# Mother_Board_ver2_0_0_under.net
KiCad netlist of a schematic drawn in EAGLE
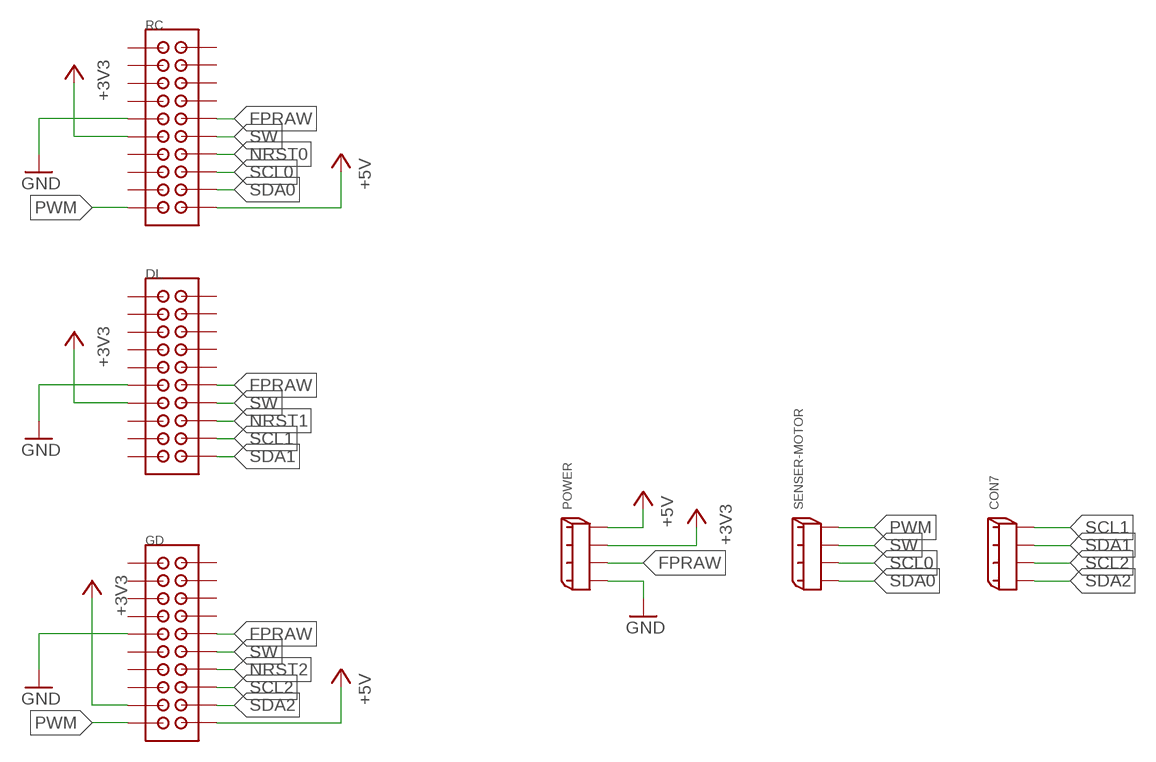
[diagram p0: schematic, sheet 1]

(export (version "E")
  (design (tool "Eeschema 10.0.6"))
  (components
    (comp (ref "CON7")
      (value "2.5_MINI-SPOX_4PIN")
      (footprint "eagle-import:2.5_MINI-SPOX_4PIN")
      (libsource (lib "eagle-import") (part "2.5_MINI-SPOX_4PIN"))
    )
    (comp (ref "DL")
      (value "2X10")
      (footprint "eagle-import:2X10")
      (libsource (lib "eagle-import") (part "2X10"))
    )
    (comp (ref "GD")
      (value "2X10")
      (footprint "eagle-import:2X10")
      (libsource (lib "eagle-import") (part "2X10"))
    )
    (comp (ref "POWER")
      (value "2.5_MINI-SPOX_4PIN")
      (footprint "eagle-import:2.5_MINI-SPOX_4PIN")
      (libsource (lib "eagle-import") (part "2.5_MINI-SPOX_4PIN"))
    )
    (comp (ref "RC")
      (value "2X10")
      (footprint "eagle-import:2X10")
      (libsource (lib "eagle-import") (part "2X10"))
    )
    (comp (ref "SENSER-MOTOR")
      (value "2.5_MINI-SPOX_4PIN")
      (footprint "eagle-import:2.5_MINI-SPOX_4PIN")
      (libsource (lib "eagle-import") (part "2.5_MINI-SPOX_4PIN"))
    )
  )
  (nets
    (net (code "1") (name "+3V3") (class "Default")
      (node (ref "DL") (pin "P$13") (pinfunction "P$13_P$13") (pintype "bidirectional"))
      (node (ref "GD") (pin "P$17") (pinfunction "P$17_P$17") (pintype "bidirectional"))
      (node (ref "POWER") (pin "P$3") (pinfunction "3_P$3") (pintype "bidirectional"))
      (node (ref "RC") (pin "P$11") (pinfunction "P$11_P$11") (pintype "bidirectional"))
    )
    (net (code "2") (name "+5V") (class "Default")
      (node (ref "GD") (pin "P$20") (pinfunction "P$20_P$20") (pintype "bidirectional"))
      (node (ref "POWER") (pin "P$4") (pinfunction "4_P$4") (pintype "bidirectional"))
      (node (ref "RC") (pin "P$20") (pinfunction "P$20_P$20") (pintype "bidirectional"))
    )
    (net (code "3") (name "FPRAW") (class "Default")
      (node (ref "DL") (pin "P$12") (pinfunction "P$12_P$12") (pintype "bidirectional"))
      (node (ref "GD") (pin "P$10") (pinfunction "P$10_P$10") (pintype "bidirectional"))
      (node (ref "POWER") (pin "P$2") (pinfunction "2_P$2") (pintype "bidirectional"))
      (node (ref "RC") (pin "P$10") (pinfunction "P$10_P$10") (pintype "bidirectional"))
    )
    (net (code "4") (name "GND") (class "Default")
      (node (ref "DL") (pin "P$11") (pinfunction "P$11_P$11") (pintype "bidirectional"))
      (node (ref "GD") (pin "P$9") (pinfunction "P$9_P$9") (pintype "bidirectional"))
      (node (ref "POWER") (pin "P$1") (pinfunction "1_P$1") (pintype "bidirectional"))
      (node (ref "RC") (pin "P$9") (pinfunction "P$9_P$9") (pintype "bidirectional"))
    )
    (net (code "5") (name "NRST0") (class "Default")
      (node (ref "RC") (pin "P$14") (pinfunction "P$14_P$14") (pintype "bidirectional"))
    )
    (net (code "6") (name "NRST1") (class "Default")
      (node (ref "DL") (pin "P$16") (pinfunction "P$16_P$16") (pintype "bidirectional"))
    )
    (net (code "7") (name "NRST2") (class "Default")
      (node (ref "GD") (pin "P$14") (pinfunction "P$14_P$14") (pintype "bidirectional"))
    )
    (net (code "8") (name "PWM") (class "Default")
      (node (ref "GD") (pin "P$19") (pinfunction "P$19_P$19") (pintype "bidirectional"))
      (node (ref "RC") (pin "P$19") (pinfunction "P$19_P$19") (pintype "bidirectional"))
      (node (ref "SENSER-MOTOR") (pin "P$4") (pinfunction "4_P$4") (pintype "bidirectional"))
    )
    (net (code "9") (name "SCL0") (class "Default")
      (node (ref "RC") (pin "P$16") (pinfunction "P$16_P$16") (pintype "bidirectional"))
      (node (ref "SENSER-MOTOR") (pin "P$2") (pinfunction "2_P$2") (pintype "bidirectional"))
    )
    (net (code "10") (name "SCL1") (class "Default")
      (node (ref "CON7") (pin "P$4") (pinfunction "4_P$4") (pintype "bidirectional"))
      (node (ref "DL") (pin "P$18") (pinfunction "P$18_P$18") (pintype "bidirectional"))
    )
    (net (code "11") (name "SCL2") (class "Default")
      (node (ref "CON7") (pin "P$2") (pinfunction "2_P$2") (pintype "bidirectional"))
      (node (ref "GD") (pin "P$16") (pinfunction "P$16_P$16") (pintype "bidirectional"))
    )
    (net (code "12") (name "SDA0") (class "Default")
      (node (ref "RC") (pin "P$18") (pinfunction "P$18_P$18") (pintype "bidirectional"))
      (node (ref "SENSER-MOTOR") (pin "P$1") (pinfunction "1_P$1") (pintype "bidirectional"))
    )
    (net (code "13") (name "SDA1") (class "Default")
      (node (ref "CON7") (pin "P$3") (pinfunction "3_P$3") (pintype "bidirectional"))
      (node (ref "DL") (pin "P$20") (pinfunction "P$20_P$20") (pintype "bidirectional"))
    )
    (net (code "14") (name "SDA2") (class "Default")
      (node (ref "CON7") (pin "P$1") (pinfunction "1_P$1") (pintype "bidirectional"))
      (node (ref "GD") (pin "P$18") (pinfunction "P$18_P$18") (pintype "bidirectional"))
    )
    (net (code "15") (name "SW") (class "Default")
      (node (ref "DL") (pin "P$14") (pinfunction "P$14_P$14") (pintype "bidirectional"))
      (node (ref "GD") (pin "P$12") (pinfunction "P$12_P$12") (pintype "bidirectional"))
      (node (ref "RC") (pin "P$12") (pinfunction "P$12_P$12") (pintype "bidirectional"))
      (node (ref "SENSER-MOTOR") (pin "P$3") (pinfunction "3_P$3") (pintype "bidirectional"))
    )
    (net (code "16") (name "unconnected-(DL-PadP$1)") (class "Default")
      (node (ref "DL") (pin "P$1") (pinfunction "P$1_P$1") (pintype "bidirectional"))
    )
    (net (code "17") (name "unconnected-(DL-PadP$2)") (class "Default")
      (node (ref "DL") (pin "P$2") (pinfunction "P$2_P$2") (pintype "bidirectional"))
    )
    (net (code "18") (name "unconnected-(DL-PadP$3)") (class "Default")
      (node (ref "DL") (pin "P$3") (pinfunction "P$3_P$3") (pintype "bidirectional"))
    )
    (net (code "19") (name "unconnected-(DL-PadP$4)") (class "Default")
      (node (ref "DL") (pin "P$4") (pinfunction "P$4_P$4") (pintype "bidirectional"))
    )
    (net (code "20") (name "unconnected-(DL-PadP$5)") (class "Default")
      (node (ref "DL") (pin "P$5") (pinfunction "P$5_P$5") (pintype "bidirectional"))
    )
    (net (code "21") (name "unconnected-(DL-PadP$6)") (class "Default")
      (node (ref "DL") (pin "P$6") (pinfunction "P$6_P$6") (pintype "bidirectional"))
    )
    (net (code "22") (name "unconnected-(DL-PadP$7)") (class "Default")
      (node (ref "DL") (pin "P$7") (pinfunction "P$7_P$7") (pintype "bidirectional"))
    )
    (net (code "23") (name "unconnected-(DL-PadP$8)") (class "Default")
      (node (ref "DL") (pin "P$8") (pinfunction "P$8_P$8") (pintype "bidirectional"))
    )
    (net (code "24") (name "unconnected-(DL-PadP$9)") (class "Default")
      (node (ref "DL") (pin "P$9") (pinfunction "P$9_P$9") (pintype "bidirectional"))
    )
    (net (code "25") (name "unconnected-(DL-PadP$10)") (class "Default")
      (node (ref "DL") (pin "P$10") (pinfunction "P$10_P$10") (pintype "bidirectional"))
    )
    (net (code "26") (name "unconnected-(DL-PadP$15)") (class "Default")
      (node (ref "DL") (pin "P$15") (pinfunction "P$15_P$15") (pintype "bidirectional"))
    )
    (net (code "27") (name "unconnected-(DL-PadP$17)") (class "Default")
      (node (ref "DL") (pin "P$17") (pinfunction "P$17_P$17") (pintype "bidirectional"))
    )
    (net (code "28") (name "unconnected-(DL-PadP$19)") (class "Default")
      (node (ref "DL") (pin "P$19") (pinfunction "P$19_P$19") (pintype "bidirectional"))
    )
    (net (code "29") (name "unconnected-(GD-PadP$1)") (class "Default")
      (node (ref "GD") (pin "P$1") (pinfunction "P$1_P$1") (pintype "bidirectional"))
    )
    (net (code "30") (name "unconnected-(GD-PadP$2)") (class "Default")
      (node (ref "GD") (pin "P$2") (pinfunction "P$2_P$2") (pintype "bidirectional"))
    )
    (net (code "31") (name "unconnected-(GD-PadP$3)") (class "Default")
      (node (ref "GD") (pin "P$3") (pinfunction "P$3_P$3") (pintype "bidirectional"))
    )
    (net (code "32") (name "unconnected-(GD-PadP$4)") (class "Default")
      (node (ref "GD") (pin "P$4") (pinfunction "P$4_P$4") (pintype "bidirectional"))
    )
    (net (code "33") (name "unconnected-(GD-PadP$5)") (class "Default")
      (node (ref "GD") (pin "P$5") (pinfunction "P$5_P$5") (pintype "bidirectional"))
    )
    (net (code "34") (name "unconnected-(GD-PadP$6)") (class "Default")
      (node (ref "GD") (pin "P$6") (pinfunction "P$6_P$6") (pintype "bidirectional"))
    )
    (net (code "35") (name "unconnected-(GD-PadP$7)") (class "Default")
      (node (ref "GD") (pin "P$7") (pinfunction "P$7_P$7") (pintype "bidirectional"))
    )
    (net (code "36") (name "unconnected-(GD-PadP$8)") (class "Default")
      (node (ref "GD") (pin "P$8") (pinfunction "P$8_P$8") (pintype "bidirectional"))
    )
    (net (code "37") (name "unconnected-(GD-PadP$11)") (class "Default")
      (node (ref "GD") (pin "P$11") (pinfunction "P$11_P$11") (pintype "bidirectional"))
    )
    (net (code "38") (name "unconnected-(GD-PadP$13)") (class "Default")
      (node (ref "GD") (pin "P$13") (pinfunction "P$13_P$13") (pintype "bidirectional"))
    )
    (net (code "39") (name "unconnected-(GD-PadP$15)") (class "Default")
      (node (ref "GD") (pin "P$15") (pinfunction "P$15_P$15") (pintype "bidirectional"))
    )
    (net (code "40") (name "unconnected-(RC-PadP$1)") (class "Default")
      (node (ref "RC") (pin "P$1") (pinfunction "P$1_P$1") (pintype "bidirectional"))
    )
    (net (code "41") (name "unconnected-(RC-PadP$2)") (class "Default")
      (node (ref "RC") (pin "P$2") (pinfunction "P$2_P$2") (pintype "bidirectional"))
    )
    (net (code "42") (name "unconnected-(RC-PadP$3)") (class "Default")
      (node (ref "RC") (pin "P$3") (pinfunction "P$3_P$3") (pintype "bidirectional"))
    )
    (net (code "43") (name "unconnected-(RC-PadP$4)") (class "Default")
      (node (ref "RC") (pin "P$4") (pinfunction "P$4_P$4") (pintype "bidirectional"))
    )
    (net (code "44") (name "unconnected-(RC-PadP$5)") (class "Default")
      (node (ref "RC") (pin "P$5") (pinfunction "P$5_P$5") (pintype "bidirectional"))
    )
    (net (code "45") (name "unconnected-(RC-PadP$6)") (class "Default")
      (node (ref "RC") (pin "P$6") (pinfunction "P$6_P$6") (pintype "bidirectional"))
    )
    (net (code "46") (name "unconnected-(RC-PadP$7)") (class "Default")
      (node (ref "RC") (pin "P$7") (pinfunction "P$7_P$7") (pintype "bidirectional"))
    )
    (net (code "47") (name "unconnected-(RC-PadP$8)") (class "Default")
      (node (ref "RC") (pin "P$8") (pinfunction "P$8_P$8") (pintype "bidirectional"))
    )
    (net (code "48") (name "unconnected-(RC-PadP$13)") (class "Default")
      (node (ref "RC") (pin "P$13") (pinfunction "P$13_P$13") (pintype "bidirectional"))
    )
    (net (code "49") (name "unconnected-(RC-PadP$15)") (class "Default")
      (node (ref "RC") (pin "P$15") (pinfunction "P$15_P$15") (pintype "bidirectional"))
    )
    (net (code "50") (name "unconnected-(RC-PadP$17)") (class "Default")
      (node (ref "RC") (pin "P$17") (pinfunction "P$17_P$17") (pintype "bidirectional"))
    )
  )
)
